# ap-pam-v4.net
KiCad netlist of a schematic drawn in Altium Designer
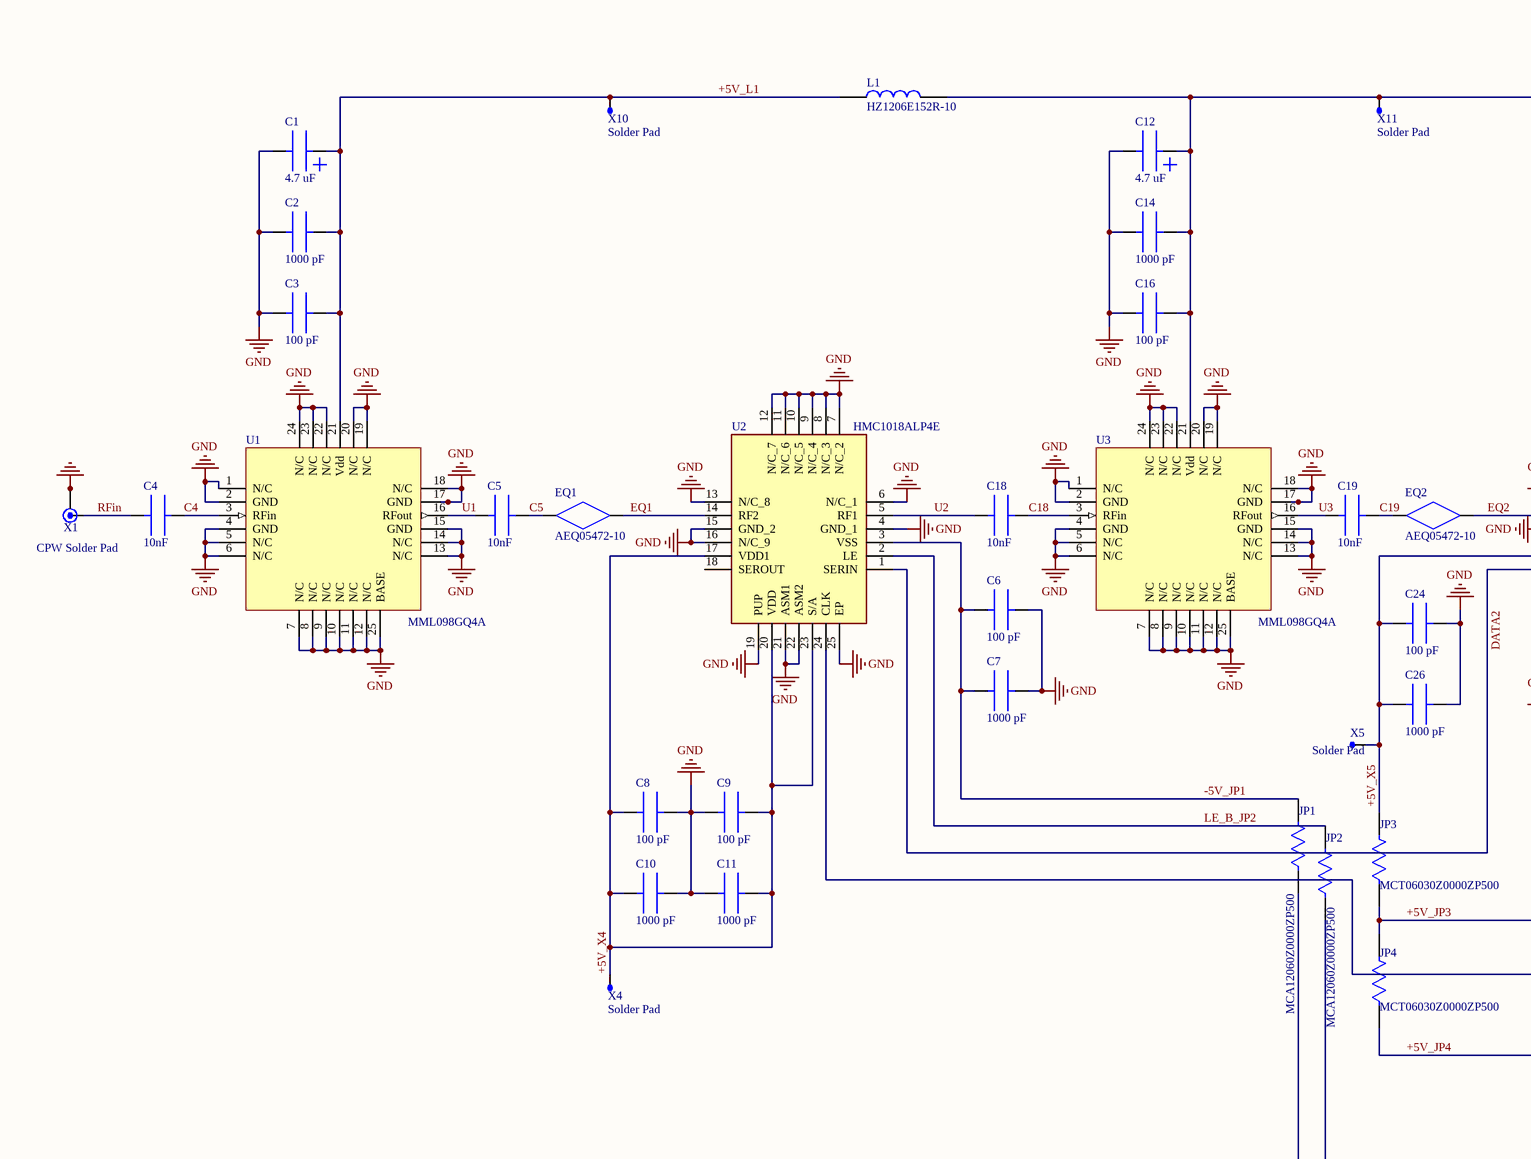
[diagram p0: ap-pam-v4.SchDoc, left]
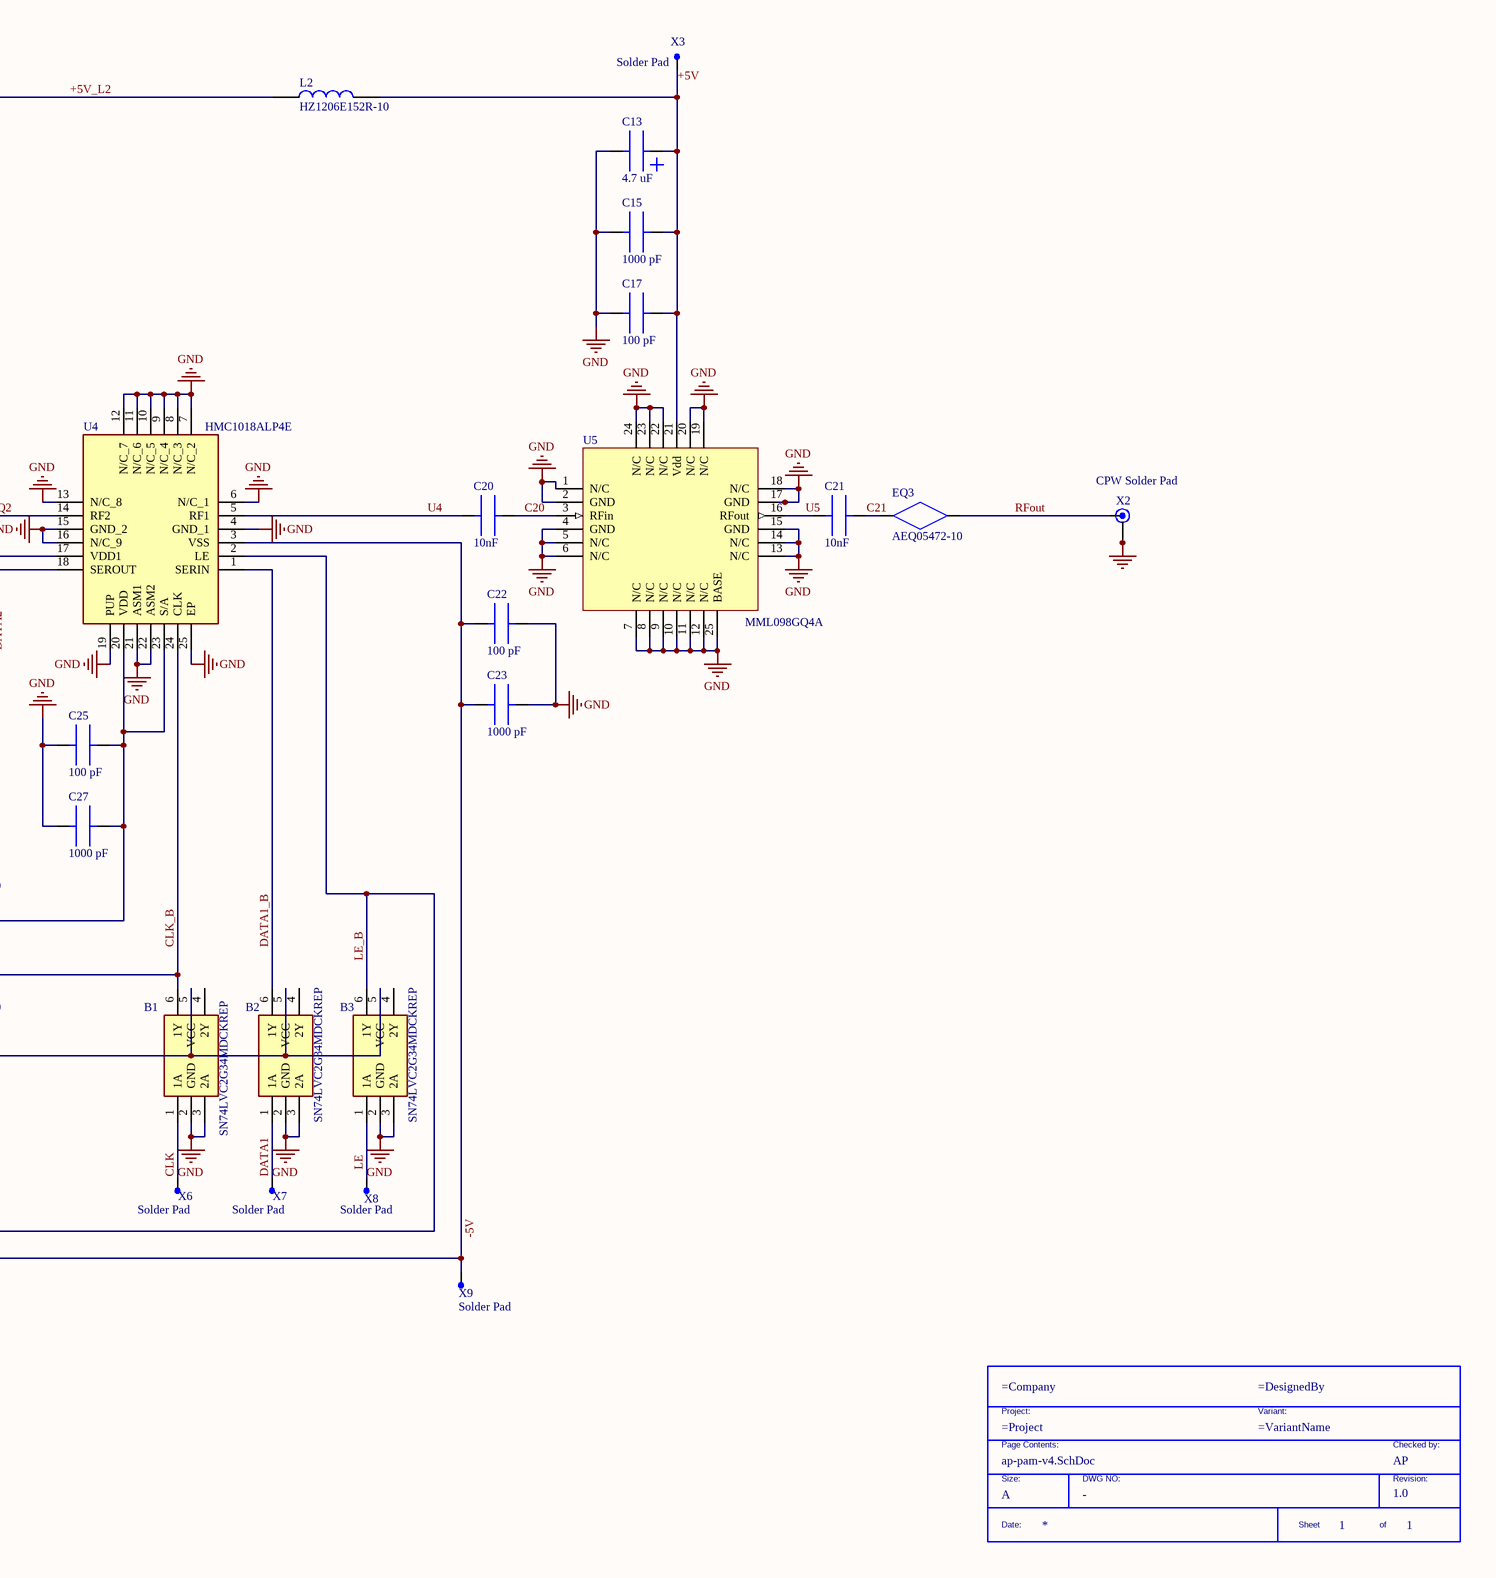
[diagram p1: ap-pam-v4.SchDoc, right]

(export (version "E")
  (design (tool "Eeschema 10.0.6"))
  (components
    (comp (ref "*")
      (value "~")
      (description "Standard Title Block")
      (fields (field (name "DWG NO") "-") (field (name "SIZE") "A") (field (name "CHECKED BY") "AP"))
      (libsource (lib "ap-pam") (part "TitleBlock"))
    )
    (comp (ref "B1")
      (value "SN74LVC2G34MDCKREP")
      (footprint "buf_SN74LVC2G34MDCKREP")
      (description "Enhanced Product Dual Buffer Gate")
      (fields (field (name "MOUSER PART NUMBER") "595-SN74L2G34MDCKREP"))
      (libsource (lib "ap-pam") (part "Buf_SN74LVC2G34MDCKREP"))
    )
    (comp (ref "B2")
      (value "SN74LVC2G34MDCKREP")
      (footprint "buf_SN74LVC2G34MDCKREP")
      (description "Enhanced Product Dual Buffer Gate")
      (fields (field (name "MOUSER PART NUMBER") "595-SN74L2G34MDCKREP"))
      (libsource (lib "ap-pam") (part "Buf_SN74LVC2G34MDCKREP"))
    )
    (comp (ref "B3")
      (value "SN74LVC2G34MDCKREP")
      (footprint "buf_SN74LVC2G34MDCKREP")
      (description "Enhanced Product Dual Buffer Gate")
      (fields (field (name "MOUSER PART NUMBER") "595-SN74L2G34MDCKREP"))
      (libsource (lib "ap-pam") (part "Buf_SN74LVC2G34MDCKREP"))
    )
    (comp (ref "C1")
      (value "4.7 uF")
      (footprint "C4_7uF")
      (fields
        (field (name "MANUFACTURER") "Vishay Sprague")
        (field (name "MANUFACTURER PART NUMBER") "TH3A475K010C2900")
      )
      (libsource (lib "ap-pam") (part "C7_4uF_TH3A475K010C2900"))
    )
    (comp (ref "C2")
      (value "1000 pF")
      (footprint "C1000pF")
      (fields
        (field (name "MANUFACTURER") "Murata")
        (field (name "MANUFACTURER PART NUMBER") "GCM1885C1H102FA16D")
      )
      (libsource (lib "ap-pam") (part "GCM1885C1H102FA16D"))
    )
    (comp (ref "C3")
      (value "100 pF")
      (footprint "C100pF")
      (description "Multilayer Ceramic Capacitors MLCC - SMD/SMT 100 pF 100 VDC 1% 0402 C0G (NP0)")
      (fields
        (field (name "MANUFACTURER") "Murata")
        (field (name "MANUFACTURER PART NUMBER") "GRM1555C2A101FA01D")
      )
      (libsource (lib "ap-pam") (part "GRM1555C2A101FA01D"))
    )
    (comp (ref "C4")
      (value "10nF")
      (footprint "C10nF")
      (fields (field (name "MANUFACTURER") "Murata") (field (name "MANUFACTURER PART NUMBER") "939113733510"))
      (libsource (lib "ap-pam") (part "C10nF_939113733510"))
    )
    (comp (ref "C5")
      (value "10nF")
      (footprint "C10nF")
      (fields (field (name "MANUFACTURER") "Murata") (field (name "MANUFACTURER PART NUMBER") "939113733510"))
      (libsource (lib "ap-pam") (part "C10nF_939113733510"))
    )
    (comp (ref "C6")
      (value "100 pF")
      (footprint "C100pF")
      (description "Multilayer Ceramic Capacitors MLCC - SMD/SMT 100 pF 100 VDC 1% 0402 C0G (NP0)")
      (fields
        (field (name "MANUFACTURER") "Murata")
        (field (name "MANUFACTURER PART NUMBER") "GRM1555C2A101FA01D")
      )
      (libsource (lib "ap-pam") (part "GRM1555C2A101FA01D"))
    )
    (comp (ref "C7")
      (value "1000 pF")
      (footprint "C1000pF")
      (fields
        (field (name "MANUFACTURER") "Murata")
        (field (name "MANUFACTURER PART NUMBER") "GCM1885C1H102FA16D")
      )
      (libsource (lib "ap-pam") (part "GCM1885C1H102FA16D"))
    )
    (comp (ref "C8")
      (value "100 pF")
      (footprint "C100pF")
      (description "Multilayer Ceramic Capacitors MLCC - SMD/SMT 100 pF 100 VDC 1% 0402 C0G (NP0)")
      (fields
        (field (name "MANUFACTURER") "Murata")
        (field (name "MANUFACTURER PART NUMBER") "GRM1555C2A101FA01D")
      )
      (libsource (lib "ap-pam") (part "GRM1555C2A101FA01D"))
    )
    (comp (ref "C9")
      (value "100 pF")
      (footprint "C100pF")
      (description "Multilayer Ceramic Capacitors MLCC - SMD/SMT 100 pF 100 VDC 1% 0402 C0G (NP0)")
      (fields
        (field (name "MANUFACTURER") "Murata")
        (field (name "MANUFACTURER PART NUMBER") "GRM1555C2A101FA01D")
      )
      (libsource (lib "ap-pam") (part "GRM1555C2A101FA01D"))
    )
    (comp (ref "C10")
      (value "1000 pF")
      (footprint "C1000pF")
      (fields
        (field (name "MANUFACTURER") "Murata")
        (field (name "MANUFACTURER PART NUMBER") "GCM1885C1H102FA16D")
      )
      (libsource (lib "ap-pam") (part "GCM1885C1H102FA16D"))
    )
    (comp (ref "C11")
      (value "1000 pF")
      (footprint "C1000pF")
      (fields
        (field (name "MANUFACTURER") "Murata")
        (field (name "MANUFACTURER PART NUMBER") "GCM1885C1H102FA16D")
      )
      (libsource (lib "ap-pam") (part "GCM1885C1H102FA16D"))
    )
    (comp (ref "C12")
      (value "4.7 uF")
      (footprint "C4_7uF")
      (fields
        (field (name "MANUFACTURER") "Vishay Sprague")
        (field (name "MANUFACTURER PART NUMBER") "TH3A475K010C2900")
      )
      (libsource (lib "ap-pam") (part "C7_4uF_TH3A475K010C2900"))
    )
    (comp (ref "C13")
      (value "4.7 uF")
      (footprint "C4_7uF")
      (fields
        (field (name "MANUFACTURER") "Vishay Sprague")
        (field (name "MANUFACTURER PART NUMBER") "TH3A475K010C2900")
      )
      (libsource (lib "ap-pam") (part "C7_4uF_TH3A475K010C2900"))
    )
    (comp (ref "C14")
      (value "1000 pF")
      (footprint "C1000pF")
      (fields
        (field (name "MANUFACTURER") "Murata")
        (field (name "MANUFACTURER PART NUMBER") "GCM1885C1H102FA16D")
      )
      (libsource (lib "ap-pam") (part "GCM1885C1H102FA16D"))
    )
    (comp (ref "C15")
      (value "1000 pF")
      (footprint "C1000pF")
      (fields
        (field (name "MANUFACTURER") "Murata")
        (field (name "MANUFACTURER PART NUMBER") "GCM1885C1H102FA16D")
      )
      (libsource (lib "ap-pam") (part "GCM1885C1H102FA16D"))
    )
    (comp (ref "C16")
      (value "100 pF")
      (footprint "C100pF")
      (description "Multilayer Ceramic Capacitors MLCC - SMD/SMT 100 pF 100 VDC 1% 0402 C0G (NP0)")
      (fields
        (field (name "MANUFACTURER") "Murata")
        (field (name "MANUFACTURER PART NUMBER") "GRM1555C2A101FA01D")
      )
      (libsource (lib "ap-pam") (part "GRM1555C2A101FA01D"))
    )
    (comp (ref "C17")
      (value "100 pF")
      (footprint "C100pF")
      (description "Multilayer Ceramic Capacitors MLCC - SMD/SMT 100 pF 100 VDC 1% 0402 C0G (NP0)")
      (fields
        (field (name "MANUFACTURER") "Murata")
        (field (name "MANUFACTURER PART NUMBER") "GRM1555C2A101FA01D")
      )
      (libsource (lib "ap-pam") (part "GRM1555C2A101FA01D"))
    )
    (comp (ref "C18")
      (value "10nF")
      (footprint "C10nF")
      (fields (field (name "MANUFACTURER") "Murata") (field (name "MANUFACTURER PART NUMBER") "939113733510"))
      (libsource (lib "ap-pam") (part "C10nF_939113733510"))
    )
    (comp (ref "C19")
      (value "10nF")
      (footprint "C10nF")
      (fields (field (name "MANUFACTURER") "Murata") (field (name "MANUFACTURER PART NUMBER") "939113733510"))
      (libsource (lib "ap-pam") (part "C10nF_939113733510"))
    )
    (comp (ref "C20")
      (value "10nF")
      (footprint "C10nF")
      (fields (field (name "MANUFACTURER") "Murata") (field (name "MANUFACTURER PART NUMBER") "939113733510"))
      (libsource (lib "ap-pam") (part "C10nF_939113733510"))
    )
    (comp (ref "C21")
      (value "10nF")
      (footprint "C10nF")
      (fields (field (name "MANUFACTURER") "Murata") (field (name "MANUFACTURER PART NUMBER") "939113733510"))
      (libsource (lib "ap-pam") (part "C10nF_939113733510"))
    )
    (comp (ref "C22")
      (value "100 pF")
      (footprint "C100pF")
      (description "Multilayer Ceramic Capacitors MLCC - SMD/SMT 100 pF 100 VDC 1% 0402 C0G (NP0)")
      (fields
        (field (name "MANUFACTURER") "Murata")
        (field (name "MANUFACTURER PART NUMBER") "GRM1555C2A101FA01D")
      )
      (libsource (lib "ap-pam") (part "GRM1555C2A101FA01D"))
    )
    (comp (ref "C23")
      (value "1000 pF")
      (footprint "C1000pF")
      (fields
        (field (name "MANUFACTURER") "Murata")
        (field (name "MANUFACTURER PART NUMBER") "GCM1885C1H102FA16D")
      )
      (libsource (lib "ap-pam") (part "GCM1885C1H102FA16D"))
    )
    (comp (ref "C24")
      (value "100 pF")
      (footprint "C100pF")
      (description "Multilayer Ceramic Capacitors MLCC - SMD/SMT 100 pF 100 VDC 1% 0402 C0G (NP0)")
      (fields
        (field (name "MANUFACTURER") "Murata")
        (field (name "MANUFACTURER PART NUMBER") "GRM1555C2A101FA01D")
      )
      (libsource (lib "ap-pam") (part "GRM1555C2A101FA01D"))
    )
    (comp (ref "C25")
      (value "100 pF")
      (footprint "C100pF")
      (description "Multilayer Ceramic Capacitors MLCC - SMD/SMT 100 pF 100 VDC 1% 0402 C0G (NP0)")
      (fields
        (field (name "MANUFACTURER") "Murata")
        (field (name "MANUFACTURER PART NUMBER") "GRM1555C2A101FA01D")
      )
      (libsource (lib "ap-pam") (part "GRM1555C2A101FA01D"))
    )
    (comp (ref "C26")
      (value "1000 pF")
      (footprint "C1000pF")
      (fields
        (field (name "MANUFACTURER") "Murata")
        (field (name "MANUFACTURER PART NUMBER") "GCM1885C1H102FA16D")
      )
      (libsource (lib "ap-pam") (part "GCM1885C1H102FA16D"))
    )
    (comp (ref "C27")
      (value "1000 pF")
      (footprint "C1000pF")
      (fields
        (field (name "MANUFACTURER") "Murata")
        (field (name "MANUFACTURER PART NUMBER") "GCM1885C1H102FA16D")
      )
      (libsource (lib "ap-pam") (part "GCM1885C1H102FA16D"))
    )
    (comp (ref "EQ1")
      (value "AEQ05472-10")
      (footprint "EQ_AEQ05472")
      (description "Rf Filter Gain Equalizer 2SMD")
      (fields (field (name "MANUFACTURER") "Knowles Dielectric Labs"))
      (libsource (lib "ap-pam") (part "EQ_AEQ05472-10"))
    )
    (comp (ref "EQ2")
      (value "AEQ05472-10")
      (footprint "EQ_AEQ05472")
      (description "Rf Filter Gain Equalizer 2SMD")
      (fields (field (name "MANUFACTURER") "Knowles Dielectric Labs"))
      (libsource (lib "ap-pam") (part "EQ_AEQ05472-10"))
    )
    (comp (ref "EQ3")
      (value "AEQ05472-10")
      (footprint "EQ_AEQ05472")
      (description "Rf Filter Gain Equalizer 2SMD")
      (fields (field (name "MANUFACTURER") "Knowles Dielectric Labs"))
      (libsource (lib "ap-pam") (part "EQ_AEQ05472-10"))
    )
    (comp (ref "JP1")
      (value "MCA12060Z0000ZP500")
      (footprint "JP_MCA12060Z0000ZP500")
      (description "Fixed Resistor, Thin Film, 0.25W, 0ohm, Surface Mount, 1206")
      (fields (field (name "MANUFACTURER") "Vishay") (field (name "POWER") "250mW"))
      (libsource (lib "ap-pam") (part "JP_MCA12060Z0000ZP500"))
    )
    (comp (ref "JP2")
      (value "MCA12060Z0000ZP500")
      (footprint "JP_MCA12060Z0000ZP500")
      (description "Fixed Resistor, Thin Film, 0.25W, 0ohm, Surface Mount, 1206")
      (fields (field (name "MANUFACTURER") "Vishay") (field (name "POWER") "250mW"))
      (libsource (lib "ap-pam") (part "JP_MCA12060Z0000ZP500"))
    )
    (comp (ref "JP3")
      (value "MCT06030Z0000ZP500")
      (footprint "JP_small_MCT06030Z0000ZP500")
      (description "Fixed Resistor, Thin Film, 0.1W, 0ohm, Surface Mount, 0603")
      (fields (field (name "MANUFACTURER") "Vishay Beyschlag") (field (name "POWER") "100mW"))
      (libsource (lib "ap-pam") (part "JP_small_MCT06030Z0000ZP500"))
    )
    (comp (ref "JP4")
      (value "MCT06030Z0000ZP500")
      (footprint "JP_small_MCT06030Z0000ZP500")
      (description "Fixed Resistor, Thin Film, 0.1W, 0ohm, Surface Mount, 0603")
      (fields (field (name "MANUFACTURER") "Vishay Beyschlag") (field (name "POWER") "100mW"))
      (libsource (lib "ap-pam") (part "JP_small_MCT06030Z0000ZP500"))
    )
    (comp (ref "L1")
      (value "HZ1206E152R-10")
      (footprint "FB_HZ1206E152R-10")
      (description "Ferrite Chip, 1 Function(s), 0.5A, 2 Pin(s)")
      (fields (field (name "MANUFACTURER") "Laird"))
      (libsource (lib "ap-pam") (part "FB_HZ1206E152R-10"))
    )
    (comp (ref "L2")
      (value "HZ1206E152R-10")
      (footprint "FB_HZ1206E152R-10")
      (description "Ferrite Chip, 1 Function(s), 0.5A, 2 Pin(s)")
      (fields (field (name "MANUFACTURER") "Laird"))
      (libsource (lib "ap-pam") (part "FB_HZ1206E152R-10"))
    )
    (comp (ref "U1")
      (value "MML098GQ4A")
      (footprint "amp_MML098GQ4A")
      (libsource (lib "ap-pam") (part "amp_MML098GQ4A"))
    )
    (comp (ref "U2")
      (value "HMC1018ALP4E")
      (footprint "Att_HMC101018ALPE")
      (description "Attenuators Attenuators")
      (fields (field (name "MOUSER PART NUMBER") "584-HMC1018ALP4E"))
      (libsource (lib "ap-pam") (part "Att_HMC1018ALP4E"))
    )
    (comp (ref "U3")
      (value "MML098GQ4A")
      (footprint "amp_MML098GQ4A")
      (libsource (lib "ap-pam") (part "amp_MML098GQ4A"))
    )
    (comp (ref "U4")
      (value "HMC1018ALP4E")
      (footprint "Att_HMC101018ALPE")
      (description "Attenuators Attenuators")
      (fields (field (name "MOUSER PART NUMBER") "584-HMC1018ALP4E"))
      (libsource (lib "ap-pam") (part "Att_HMC1018ALP4E"))
    )
    (comp (ref "U5")
      (value "MML098GQ4A")
      (footprint "amp_MML098GQ4A")
      (libsource (lib "ap-pam") (part "amp_MML098GQ4A"))
    )
    (comp (ref "X1")
      (value "CPW Solder Pad")
      (footprint "CPW Edge Connector")
      (description "Solder pad for RF Coplanar Waveguide Rogers 4350B Thickness 0.020\" Copper 1oz")
      (libsource (lib "ap-pam") (part "RF  CPW Solder Pad"))
    )
    (comp (ref "X2")
      (value "CPW Solder Pad")
      (footprint "CPW Edge Connector")
      (description "Solder pad for RF Coplanar Waveguide Rogers 4350B Thickness 0.020\" Copper 1oz")
      (libsource (lib "ap-pam") (part "RF  CPW Solder Pad"))
    )
    (comp (ref "X3")
      (value "Solder Pad")
      (footprint "Solder Pad")
      (description "Pad to solder wires to")
      (libsource (lib "ap-pam") (part "Solder Pad"))
    )
    (comp (ref "X4")
      (value "Solder Pad")
      (footprint "Solder Pad")
      (description "Pad to solder wires to")
      (libsource (lib "ap-pam") (part "Solder Pad"))
    )
    (comp (ref "X5")
      (value "Solder Pad")
      (footprint "Solder Pad")
      (description "Pad to solder wires to")
      (libsource (lib "ap-pam") (part "Solder Pad"))
    )
    (comp (ref "X6")
      (value "Solder Pad")
      (footprint "Solder Pad")
      (description "Pad to solder wires to")
      (libsource (lib "ap-pam") (part "Solder Pad"))
    )
    (comp (ref "X7")
      (value "Solder Pad")
      (footprint "Solder Pad")
      (description "Pad to solder wires to")
      (libsource (lib "ap-pam") (part "Solder Pad"))
    )
    (comp (ref "X8")
      (value "Solder Pad")
      (footprint "Solder Pad")
      (description "Pad to solder wires to")
      (libsource (lib "ap-pam") (part "Solder Pad"))
    )
    (comp (ref "X9")
      (value "Solder Pad")
      (footprint "Solder Pad")
      (description "Pad to solder wires to")
      (libsource (lib "ap-pam") (part "Solder Pad"))
    )
    (comp (ref "X10")
      (value "Solder Pad")
      (footprint "Solder Pad")
      (description "Pad to solder wires to")
      (libsource (lib "ap-pam") (part "Solder Pad"))
    )
    (comp (ref "X11")
      (value "Solder Pad")
      (footprint "Solder Pad")
      (description "Pad to solder wires to")
      (libsource (lib "ap-pam") (part "Solder Pad"))
    )
  )
  (nets
    (net (code "1") (name "/+5V") (class "Default")
      (node (ref "C13") (pin "1") (pinfunction "+_1") (pintype "passive"))
      (node (ref "C15") (pin "1") (pinfunction "1_1") (pintype "passive"))
      (node (ref "C17") (pin "1") (pinfunction "1_1") (pintype "passive"))
      (node (ref "L2") (pin "2") (pinfunction "2_2") (pintype "passive"))
      (node (ref "U5") (pin "21") (pinfunction "Vdd_21") (pintype "power_in"))
      (node (ref "X3") (pin "1") (pinfunction "1_1") (pintype "passive"))
    )
    (net (code "2") (name "/+5V_JP3") (class "Default")
      (node (ref "C25") (pin "1") (pinfunction "1_1") (pintype "passive"))
      (node (ref "C27") (pin "1") (pinfunction "1_1") (pintype "passive"))
      (node (ref "JP3") (pin "1") (pinfunction "1_1") (pintype "passive"))
      (node (ref "JP4") (pin "2") (pinfunction "2_2") (pintype "passive"))
      (node (ref "U4") (pin "20") (pinfunction "VDD_20") (pintype "passive"))
      (node (ref "U4") (pin "23") (pinfunction "S/A_23") (pintype "passive"))
    )
    (net (code "3") (name "/+5V_JP4") (class "Default")
      (node (ref "B1") (pin "5") (pinfunction "VCC_5") (pintype "passive"))
      (node (ref "B2") (pin "5") (pinfunction "VCC_5") (pintype "passive"))
      (node (ref "B3") (pin "5") (pinfunction "VCC_5") (pintype "passive"))
      (node (ref "JP4") (pin "1") (pinfunction "1_1") (pintype "passive"))
    )
    (net (code "4") (name "/+5V_L1") (class "Default")
      (node (ref "C1") (pin "1") (pinfunction "+_1") (pintype "passive"))
      (node (ref "C2") (pin "1") (pinfunction "1_1") (pintype "passive"))
      (node (ref "C3") (pin "1") (pinfunction "1_1") (pintype "passive"))
      (node (ref "L1") (pin "1") (pinfunction "1_1") (pintype "passive"))
      (node (ref "U1") (pin "21") (pinfunction "Vdd_21") (pintype "power_in"))
      (node (ref "X10") (pin "1") (pinfunction "1_1") (pintype "passive"))
    )
    (net (code "5") (name "/+5V_L2") (class "Default")
      (node (ref "C12") (pin "1") (pinfunction "+_1") (pintype "passive"))
      (node (ref "C14") (pin "1") (pinfunction "1_1") (pintype "passive"))
      (node (ref "C16") (pin "1") (pinfunction "1_1") (pintype "passive"))
      (node (ref "L1") (pin "2") (pinfunction "2_2") (pintype "passive"))
      (node (ref "L2") (pin "1") (pinfunction "1_1") (pintype "passive"))
      (node (ref "U3") (pin "21") (pinfunction "Vdd_21") (pintype "power_in"))
      (node (ref "X11") (pin "1") (pinfunction "1_1") (pintype "passive"))
    )
    (net (code "6") (name "/+5V_X4") (class "Default")
      (node (ref "C10") (pin "1") (pinfunction "1_1") (pintype "passive"))
      (node (ref "C11") (pin "1") (pinfunction "1_1") (pintype "passive"))
      (node (ref "C8") (pin "1") (pinfunction "1_1") (pintype "passive"))
      (node (ref "C9") (pin "1") (pinfunction "1_1") (pintype "passive"))
      (node (ref "U2") (pin "17") (pinfunction "VDD1_17") (pintype "passive"))
      (node (ref "U2") (pin "20") (pinfunction "VDD_20") (pintype "passive"))
      (node (ref "U2") (pin "23") (pinfunction "S/A_23") (pintype "passive"))
      (node (ref "X4") (pin "1") (pinfunction "1_1") (pintype "passive"))
    )
    (net (code "7") (name "/+5V_X5") (class "Default")
      (node (ref "C24") (pin "1") (pinfunction "1_1") (pintype "passive"))
      (node (ref "C26") (pin "1") (pinfunction "1_1") (pintype "passive"))
      (node (ref "JP3") (pin "2") (pinfunction "2_2") (pintype "passive"))
      (node (ref "U4") (pin "17") (pinfunction "VDD1_17") (pintype "passive"))
      (node (ref "X5") (pin "1") (pinfunction "1_1") (pintype "passive"))
    )
    (net (code "8") (name "/-5V") (class "Default")
      (node (ref "C22") (pin "1") (pinfunction "1_1") (pintype "passive"))
      (node (ref "C23") (pin "1") (pinfunction "1_1") (pintype "passive"))
      (node (ref "JP1") (pin "1") (pinfunction "1_1") (pintype "passive"))
      (node (ref "U4") (pin "3") (pinfunction "VSS_3") (pintype "passive"))
      (node (ref "X9") (pin "1") (pinfunction "1_1") (pintype "passive"))
    )
    (net (code "9") (name "/-5V_JP1") (class "Default")
      (node (ref "C6") (pin "1") (pinfunction "1_1") (pintype "passive"))
      (node (ref "C7") (pin "1") (pinfunction "1_1") (pintype "passive"))
      (node (ref "JP1") (pin "2") (pinfunction "2_2") (pintype "passive"))
      (node (ref "U2") (pin "3") (pinfunction "VSS_3") (pintype "passive"))
    )
    (net (code "10") (name "/C4") (class "Default")
      (node (ref "C4") (pin "2") (pinfunction "2_2") (pintype "passive"))
      (node (ref "U1") (pin "3") (pinfunction "RFin_3") (pintype "input"))
    )
    (net (code "11") (name "/C5") (class "Default")
      (node (ref "C5") (pin "2") (pinfunction "2_2") (pintype "passive"))
      (node (ref "EQ1") (pin "1") (pinfunction "1_1") (pintype "passive"))
    )
    (net (code "12") (name "/C18") (class "Default")
      (node (ref "C18") (pin "2") (pinfunction "2_2") (pintype "passive"))
      (node (ref "U3") (pin "3") (pinfunction "RFin_3") (pintype "input"))
    )
    (net (code "13") (name "/C19") (class "Default")
      (node (ref "C19") (pin "2") (pinfunction "2_2") (pintype "passive"))
      (node (ref "EQ2") (pin "1") (pinfunction "1_1") (pintype "passive"))
    )
    (net (code "14") (name "/C20") (class "Default")
      (node (ref "C20") (pin "2") (pinfunction "2_2") (pintype "passive"))
      (node (ref "U5") (pin "3") (pinfunction "RFin_3") (pintype "input"))
    )
    (net (code "15") (name "/C21") (class "Default")
      (node (ref "C21") (pin "2") (pinfunction "2_2") (pintype "passive"))
      (node (ref "EQ3") (pin "1") (pinfunction "1_1") (pintype "passive"))
    )
    (net (code "16") (name "/CLK") (class "Default")
      (node (ref "B1") (pin "1") (pinfunction "1A_1") (pintype "passive"))
      (node (ref "X6") (pin "1") (pinfunction "1_1") (pintype "passive"))
    )
    (net (code "17") (name "/CLK_B") (class "Default")
      (node (ref "B1") (pin "6") (pinfunction "1Y_6") (pintype "passive"))
      (node (ref "U2") (pin "24") (pinfunction "CLK_24") (pintype "passive"))
      (node (ref "U4") (pin "24") (pinfunction "CLK_24") (pintype "passive"))
    )
    (net (code "18") (name "/DATA1") (class "Default")
      (node (ref "B2") (pin "1") (pinfunction "1A_1") (pintype "passive"))
      (node (ref "X7") (pin "1") (pinfunction "1_1") (pintype "passive"))
    )
    (net (code "19") (name "/DATA1_B") (class "Default")
      (node (ref "B2") (pin "6") (pinfunction "1Y_6") (pintype "passive"))
      (node (ref "U4") (pin "1") (pinfunction "SERIN_1") (pintype "passive"))
    )
    (net (code "20") (name "/DATA2") (class "Default")
      (node (ref "U2") (pin "1") (pinfunction "SERIN_1") (pintype "passive"))
      (node (ref "U4") (pin "18") (pinfunction "SEROUT_18") (pintype "passive"))
    )
    (net (code "21") (name "/EQ1") (class "Default")
      (node (ref "EQ1") (pin "2") (pinfunction "2_2") (pintype "passive"))
      (node (ref "U2") (pin "14") (pinfunction "RF2_14") (pintype "passive"))
    )
    (net (code "22") (name "/EQ2") (class "Default")
      (node (ref "EQ2") (pin "2") (pinfunction "2_2") (pintype "passive"))
      (node (ref "U4") (pin "14") (pinfunction "RF2_14") (pintype "passive"))
    )
    (net (code "23") (name "/LE") (class "Default")
      (node (ref "B3") (pin "1") (pinfunction "1A_1") (pintype "passive"))
      (node (ref "X8") (pin "1") (pinfunction "1_1") (pintype "passive"))
    )
    (net (code "24") (name "/LE_B") (class "Default")
      (node (ref "B3") (pin "6") (pinfunction "1Y_6") (pintype "passive"))
      (node (ref "JP2") (pin "1") (pinfunction "1_1") (pintype "passive"))
      (node (ref "U4") (pin "2") (pinfunction "LE_2") (pintype "passive"))
    )
    (net (code "25") (name "/LE_B_JP2") (class "Default")
      (node (ref "JP2") (pin "2") (pinfunction "2_2") (pintype "passive"))
      (node (ref "U2") (pin "2") (pinfunction "LE_2") (pintype "passive"))
    )
    (net (code "26") (name "/RFin") (class "Default")
      (node (ref "C4") (pin "1") (pinfunction "1_1") (pintype "passive"))
      (node (ref "X1") (pin "1") (pinfunction "1_1") (pintype "passive"))
    )
    (net (code "27") (name "/RFout") (class "Default")
      (node (ref "EQ3") (pin "2") (pinfunction "2_2") (pintype "passive"))
      (node (ref "X2") (pin "1") (pinfunction "1_1") (pintype "passive"))
    )
    (net (code "28") (name "/U1") (class "Default")
      (node (ref "C5") (pin "1") (pinfunction "1_1") (pintype "passive"))
      (node (ref "U1") (pin "16") (pinfunction "RFout_16") (pintype "output"))
    )
    (net (code "29") (name "/U2") (class "Default")
      (node (ref "C18") (pin "1") (pinfunction "1_1") (pintype "passive"))
      (node (ref "U2") (pin "5") (pinfunction "RF1_5") (pintype "passive"))
    )
    (net (code "30") (name "/U3") (class "Default")
      (node (ref "C19") (pin "1") (pinfunction "1_1") (pintype "passive"))
      (node (ref "U3") (pin "16") (pinfunction "RFout_16") (pintype "output"))
    )
    (net (code "31") (name "/U4") (class "Default")
      (node (ref "C20") (pin "1") (pinfunction "1_1") (pintype "passive"))
      (node (ref "U4") (pin "5") (pinfunction "RF1_5") (pintype "passive"))
    )
    (net (code "32") (name "/U5") (class "Default")
      (node (ref "C21") (pin "1") (pinfunction "1_1") (pintype "passive"))
      (node (ref "U5") (pin "16") (pinfunction "RFout_16") (pintype "output"))
    )
    (net (code "33") (name "GND") (class "Default")
      (node (ref "B1") (pin "2") (pinfunction "GND_2") (pintype "passive"))
      (node (ref "B1") (pin "3") (pinfunction "2A_3") (pintype "passive"))
      (node (ref "B2") (pin "2") (pinfunction "GND_2") (pintype "passive"))
      (node (ref "B2") (pin "3") (pinfunction "2A_3") (pintype "passive"))
      (node (ref "B3") (pin "2") (pinfunction "GND_2") (pintype "passive"))
      (node (ref "B3") (pin "3") (pinfunction "2A_3") (pintype "passive"))
      (node (ref "C1") (pin "2") (pinfunction "2_2") (pintype "passive"))
      (node (ref "C10") (pin "2") (pinfunction "2_2") (pintype "passive"))
      (node (ref "C11") (pin "2") (pinfunction "2_2") (pintype "passive"))
      (node (ref "C12") (pin "2") (pinfunction "2_2") (pintype "passive"))
      (node (ref "C13") (pin "2") (pinfunction "2_2") (pintype "passive"))
      (node (ref "C14") (pin "2") (pinfunction "2_2") (pintype "passive"))
      (node (ref "C15") (pin "2") (pinfunction "2_2") (pintype "passive"))
      (node (ref "C16") (pin "2") (pinfunction "2_2") (pintype "passive"))
      (node (ref "C17") (pin "2") (pinfunction "2_2") (pintype "passive"))
      (node (ref "C2") (pin "2") (pinfunction "2_2") (pintype "passive"))
      (node (ref "C22") (pin "2") (pinfunction "2_2") (pintype "passive"))
      (node (ref "C23") (pin "2") (pinfunction "2_2") (pintype "passive"))
      (node (ref "C24") (pin "2") (pinfunction "2_2") (pintype "passive"))
      (node (ref "C25") (pin "2") (pinfunction "2_2") (pintype "passive"))
      (node (ref "C26") (pin "2") (pinfunction "2_2") (pintype "passive"))
      (node (ref "C27") (pin "2") (pinfunction "2_2") (pintype "passive"))
      (node (ref "C3") (pin "2") (pinfunction "2_2") (pintype "passive"))
      (node (ref "C6") (pin "2") (pinfunction "2_2") (pintype "passive"))
      (node (ref "C7") (pin "2") (pinfunction "2_2") (pintype "passive"))
      (node (ref "C8") (pin "2") (pinfunction "2_2") (pintype "passive"))
      (node (ref "C9") (pin "2") (pinfunction "2_2") (pintype "passive"))
      (node (ref "U1") (pin "1") (pinfunction "N/C_1") (pintype "passive"))
      (node (ref "U1") (pin "10") (pinfunction "N/C_10") (pintype "passive"))
      (node (ref "U1") (pin "11") (pinfunction "N/C_11") (pintype "passive"))
      (node (ref "U1") (pin "12") (pinfunction "N/C_12") (pintype "passive"))
      (node (ref "U1") (pin "13") (pinfunction "N/C_13") (pintype "passive"))
      (node (ref "U1") (pin "14") (pinfunction "N/C_14") (pintype "passive"))
      (node (ref "U1") (pin "15") (pinfunction "GND_15") (pintype "power_in"))
      (node (ref "U1") (pin "17") (pinfunction "GND_17") (pintype "power_in"))
      (node (ref "U1") (pin "18") (pinfunction "N/C_18") (pintype "passive"))
      (node (ref "U1") (pin "19") (pinfunction "N/C_19") (pintype "passive"))
      (node (ref "U1") (pin "2") (pinfunction "GND_2") (pintype "power_in"))
      (node (ref "U1") (pin "20") (pinfunction "N/C_20") (pintype "passive"))
      (node (ref "U1") (pin "22") (pinfunction "N/C_22") (pintype "passive"))
      (node (ref "U1") (pin "23") (pinfunction "N/C_23") (pintype "passive"))
      (node (ref "U1") (pin "24") (pinfunction "N/C_24") (pintype "passive"))
      (node (ref "U1") (pin "25") (pinfunction "BASE_25") (pintype "power_in"))
      (node (ref "U1") (pin "4") (pinfunction "GND_4") (pintype "power_in"))
      (node (ref "U1") (pin "5") (pinfunction "N/C_5") (pintype "passive"))
      (node (ref "U1") (pin "6") (pinfunction "N/C_6") (pintype "passive"))
      (node (ref "U1") (pin "7") (pinfunction "N/C_7") (pintype "passive"))
      (node (ref "U1") (pin "8") (pinfunction "N/C_8") (pintype "passive"))
      (node (ref "U1") (pin "9") (pinfunction "N/C_9") (pintype "passive"))
      (node (ref "U2") (pin "10") (pinfunction "N/C_5_10") (pintype "passive"))
      (node (ref "U2") (pin "11") (pinfunction "N/C_6_11") (pintype "passive"))
      (node (ref "U2") (pin "12") (pinfunction "N/C_7_12") (pintype "passive"))
      (node (ref "U2") (pin "13") (pinfunction "N/C_8_13") (pintype "passive"))
      (node (ref "U2") (pin "15") (pinfunction "GND_2_15") (pintype "passive"))
      (node (ref "U2") (pin "16") (pinfunction "N/C_9_16") (pintype "passive"))
      (node (ref "U2") (pin "19") (pinfunction "PUP_19") (pintype "passive"))
      (node (ref "U2") (pin "21") (pinfunction "ASM1_21") (pintype "passive"))
      (node (ref "U2") (pin "22") (pinfunction "ASM2_22") (pintype "passive"))
      (node (ref "U2") (pin "25") (pinfunction "EP_25") (pintype "passive"))
      (node (ref "U2") (pin "4") (pinfunction "GND_1_4") (pintype "passive"))
      (node (ref "U2") (pin "6") (pinfunction "N/C_1_6") (pintype "passive"))
      (node (ref "U2") (pin "7") (pinfunction "N/C_2_7") (pintype "passive"))
      (node (ref "U2") (pin "8") (pinfunction "N/C_3_8") (pintype "passive"))
      (node (ref "U2") (pin "9") (pinfunction "N/C_4_9") (pintype "passive"))
      (node (ref "U3") (pin "1") (pinfunction "N/C_1") (pintype "passive"))
      (node (ref "U3") (pin "10") (pinfunction "N/C_10") (pintype "passive"))
      (node (ref "U3") (pin "11") (pinfunction "N/C_11") (pintype "passive"))
      (node (ref "U3") (pin "12") (pinfunction "N/C_12") (pintype "passive"))
      (node (ref "U3") (pin "13") (pinfunction "N/C_13") (pintype "passive"))
      (node (ref "U3") (pin "14") (pinfunction "N/C_14") (pintype "passive"))
      (node (ref "U3") (pin "15") (pinfunction "GND_15") (pintype "power_in"))
      (node (ref "U3") (pin "17") (pinfunction "GND_17") (pintype "power_in"))
      (node (ref "U3") (pin "18") (pinfunction "N/C_18") (pintype "passive"))
      (node (ref "U3") (pin "19") (pinfunction "N/C_19") (pintype "passive"))
      (node (ref "U3") (pin "2") (pinfunction "GND_2") (pintype "power_in"))
      (node (ref "U3") (pin "20") (pinfunction "N/C_20") (pintype "passive"))
      (node (ref "U3") (pin "22") (pinfunction "N/C_22") (pintype "passive"))
      (node (ref "U3") (pin "23") (pinfunction "N/C_23") (pintype "passive"))
      (node (ref "U3") (pin "24") (pinfunction "N/C_24") (pintype "passive"))
      (node (ref "U3") (pin "25") (pinfunction "BASE_25") (pintype "power_in"))
      (node (ref "U3") (pin "4") (pinfunction "GND_4") (pintype "power_in"))
      (node (ref "U3") (pin "5") (pinfunction "N/C_5") (pintype "passive"))
      (node (ref "U3") (pin "6") (pinfunction "N/C_6") (pintype "passive"))
      (node (ref "U3") (pin "7") (pinfunction "N/C_7") (pintype "passive"))
      (node (ref "U3") (pin "8") (pinfunction "N/C_8") (pintype "passive"))
      (node (ref "U3") (pin "9") (pinfunction "N/C_9") (pintype "passive"))
      (node (ref "U4") (pin "10") (pinfunction "N/C_5_10") (pintype "passive"))
      (node (ref "U4") (pin "11") (pinfunction "N/C_6_11") (pintype "passive"))
      (node (ref "U4") (pin "12") (pinfunction "N/C_7_12") (pintype "passive"))
      (node (ref "U4") (pin "13") (pinfunction "N/C_8_13") (pintype "passive"))
      (node (ref "U4") (pin "15") (pinfunction "GND_2_15") (pintype "passive"))
      (node (ref "U4") (pin "16") (pinfunction "N/C_9_16") (pintype "passive"))
      (node (ref "U4") (pin "19") (pinfunction "PUP_19") (pintype "passive"))
      (node (ref "U4") (pin "21") (pinfunction "ASM1_21") (pintype "passive"))
      (node (ref "U4") (pin "22") (pinfunction "ASM2_22") (pintype "passive"))
      (node (ref "U4") (pin "25") (pinfunction "EP_25") (pintype "passive"))
      (node (ref "U4") (pin "4") (pinfunction "GND_1_4") (pintype "passive"))
      (node (ref "U4") (pin "6") (pinfunction "N/C_1_6") (pintype "passive"))
      (node (ref "U4") (pin "7") (pinfunction "N/C_2_7") (pintype "passive"))
      (node (ref "U4") (pin "8") (pinfunction "N/C_3_8") (pintype "passive"))
      (node (ref "U4") (pin "9") (pinfunction "N/C_4_9") (pintype "passive"))
      (node (ref "U5") (pin "1") (pinfunction "N/C_1") (pintype "passive"))
      (node (ref "U5") (pin "10") (pinfunction "N/C_10") (pintype "passive"))
      (node (ref "U5") (pin "11") (pinfunction "N/C_11") (pintype "passive"))
      (node (ref "U5") (pin "12") (pinfunction "N/C_12") (pintype "passive"))
      (node (ref "U5") (pin "13") (pinfunction "N/C_13") (pintype "passive"))
      (node (ref "U5") (pin "14") (pinfunction "N/C_14") (pintype "passive"))
      (node (ref "U5") (pin "15") (pinfunction "GND_15") (pintype "power_in"))
      (node (ref "U5") (pin "17") (pinfunction "GND_17") (pintype "power_in"))
      (node (ref "U5") (pin "18") (pinfunction "N/C_18") (pintype "passive"))
      (node (ref "U5") (pin "19") (pinfunction "N/C_19") (pintype "passive"))
      (node (ref "U5") (pin "2") (pinfunction "GND_2") (pintype "power_in"))
      (node (ref "U5") (pin "20") (pinfunction "N/C_20") (pintype "passive"))
      (node (ref "U5") (pin "22") (pinfunction "N/C_22") (pintype "passive"))
      (node (ref "U5") (pin "23") (pinfunction "N/C_23") (pintype "passive"))
      (node (ref "U5") (pin "24") (pinfunction "N/C_24") (pintype "passive"))
      (node (ref "U5") (pin "25") (pinfunction "BASE_25") (pintype "power_in"))
      (node (ref "U5") (pin "4") (pinfunction "GND_4") (pintype "power_in"))
      (node (ref "U5") (pin "5") (pinfunction "N/C_5") (pintype "passive"))
      (node (ref "U5") (pin "6") (pinfunction "N/C_6") (pintype "passive"))
      (node (ref "U5") (pin "7") (pinfunction "N/C_7") (pintype "passive"))
      (node (ref "U5") (pin "8") (pinfunction "N/C_8") (pintype "passive"))
      (node (ref "U5") (pin "9") (pinfunction "N/C_9") (pintype "passive"))
      (node (ref "X1") (pin "2") (pinfunction "2_2") (pintype "passive"))
      (node (ref "X1") (pin "3") (pinfunction "3_3") (pintype "passive"))
      (node (ref "X2") (pin "2") (pinfunction "2_2") (pintype "passive"))
      (node (ref "X2") (pin "3") (pinfunction "3_3") (pintype "passive"))
    )
    (net (code "34") (name "unconnected-(B1-2Y-Pad4)") (class "Default")
      (node (ref "B1") (pin "4") (pinfunction "2Y_4") (pintype "passive"))
    )
    (net (code "35") (name "unconnected-(B2-2Y-Pad4)") (class "Default")
      (node (ref "B2") (pin "4") (pinfunction "2Y_4") (pintype "passive"))
    )
    (net (code "36") (name "unconnected-(B3-2Y-Pad4)") (class "Default")
      (node (ref "B3") (pin "4") (pinfunction "2Y_4") (pintype "passive"))
    )
    (net (code "37") (name "unconnected-(U2-SEROUT-Pad18)") (class "Default")
      (node (ref "U2") (pin "18") (pinfunction "SEROUT_18") (pintype "passive"))
    )
  )
)
